# EHT_Dimmer.net
KiCad netlist of a schematic drawn in EAGLE
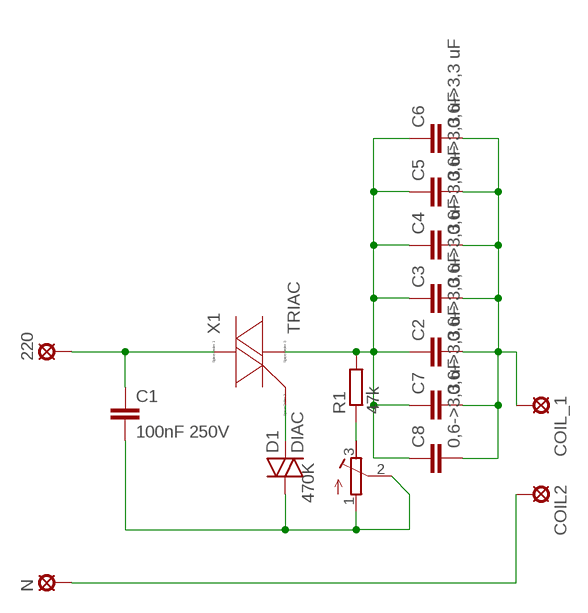
[diagram p0: schematic, sheet 1]

(export (version "E")
  (design (tool "Eeschema 10.0.6"))
  (components
    (comp (ref "220")
      (value "LSP10")
      (footprint "eagle-import:LSP10")
      (libsource (lib "eagle-import") (part "LSP10"))
    )
    (comp (ref "470K")
      (value "R-TRIMM3339P")
      (footprint "eagle-import:RTRIM3339P")
      (libsource (lib "eagle-import") (part "R-TRIMM3339P"))
    )
    (comp (ref "C1")
      (value "100nF 250V")
      (footprint "eagle-import:C102_152-062X184")
      (libsource (lib "eagle-import") (part "C-EU102_152-062X184"))
    )
    (comp (ref "C2")
      (value "0,6->3,3 uF")
      (footprint "eagle-import:C102_152-062X184")
      (libsource (lib "eagle-import") (part "C-EU102_152-062X184"))
    )
    (comp (ref "C3")
      (value "0,6->3,3 uF")
      (footprint "eagle-import:C102_152-062X184")
      (libsource (lib "eagle-import") (part "C-EU102_152-062X184"))
    )
    (comp (ref "C4")
      (value "0,6->3,3 uF")
      (footprint "eagle-import:C102_152-062X184")
      (libsource (lib "eagle-import") (part "C-EU102_152-062X184"))
    )
    (comp (ref "C5")
      (value "0,6->3,3 uF")
      (footprint "eagle-import:C102_152-062X184")
      (libsource (lib "eagle-import") (part "C-EU102_152-062X184"))
    )
    (comp (ref "C6")
      (value "0,6->3,3 uF")
      (footprint "eagle-import:C102_152-062X184")
      (libsource (lib "eagle-import") (part "C-EU102_152-062X184"))
    )
    (comp (ref "C7")
      (value "0,6->3,3 uF")
      (footprint "eagle-import:C102_152-062X184")
      (libsource (lib "eagle-import") (part "C-EU102_152-062X184"))
    )
    (comp (ref "C8")
      (value "0,6->3,3 uF")
      (footprint "eagle-import:C102_152-062X184")
      (libsource (lib "eagle-import") (part "C-EU102_152-062X184"))
    )
    (comp (ref "COIL2")
      (value "LSP10")
      (footprint "eagle-import:LSP10")
      (libsource (lib "eagle-import") (part "LSP10"))
    )
    (comp (ref "COIL_1")
      (value "LSP10")
      (footprint "eagle-import:LSP10")
      (libsource (lib "eagle-import") (part "LSP10"))
    )
    (comp (ref "D1")
      (value "DIAC")
      (footprint "eagle-import:GT32")
      (libsource (lib "eagle-import") (part "DIAC-GT32"))
    )
    (comp (ref "N")
      (value "LSP10")
      (footprint "eagle-import:LSP10")
      (libsource (lib "eagle-import") (part "LSP10"))
    )
    (comp (ref "R1")
      (value "47k")
      (footprint "eagle-import:0207_10")
      (libsource (lib "eagle-import") (part "R-EU_0207/10"))
    )
    (comp (ref "X1")
      (value "TRIAC")
      (footprint "eagle-import:BR220S")
      (libsource (lib "eagle-import") (part "TRIAC"))
    )
  )
  (nets
    (net (code "1") (name "Net-(470K-A)") (class "Default")
      (node (ref "470K") (pin "1") (pinfunction "A_1") (pintype "passive"))
      (node (ref "470K") (pin "2") (pinfunction "S_2") (pintype "passive"))
      (node (ref "C1") (pin "2") (pinfunction "2_2") (pintype "passive"))
      (node (ref "D1") (pin "1") (pinfunction "1_1") (pintype "passive"))
    )
    (net (code "2") (name "Net-(470K-E)") (class "Default")
      (node (ref "470K") (pin "3") (pinfunction "E_3") (pintype "passive"))
      (node (ref "R1") (pin "1") (pinfunction "1_1") (pintype "passive"))
    )
    (net (code "3") (name "Net-(C2-Pad2)") (class "Default")
      (node (ref "C2") (pin "2") (pinfunction "2_2") (pintype "passive"))
      (node (ref "C3") (pin "2") (pinfunction "2_2") (pintype "passive"))
      (node (ref "C4") (pin "2") (pinfunction "2_2") (pintype "passive"))
      (node (ref "C5") (pin "2") (pinfunction "2_2") (pintype "passive"))
      (node (ref "C6") (pin "2") (pinfunction "2_2") (pintype "passive"))
      (node (ref "C7") (pin "2") (pinfunction "2_2") (pintype "passive"))
      (node (ref "C8") (pin "2") (pinfunction "2_2") (pintype "passive"))
      (node (ref "COIL_1") (pin "MP") (pinfunction "MP_MP") (pintype "passive"))
    )
    (net (code "4") (name "Net-(COIL2-PadMP)") (class "Default")
      (node (ref "COIL2") (pin "MP") (pinfunction "MP_MP") (pintype "passive"))
      (node (ref "N") (pin "MP") (pinfunction "MP_MP") (pintype "passive"))
    )
    (net (code "5") (name "Net-(X1-G)") (class "Default")
      (node (ref "D1") (pin "2") (pinfunction "2_2") (pintype "passive"))
      (node (ref "X1") (pin "T1") (pinfunction "G_T1") (pintype "passive"))
    )
    (net (code "6") (name "Net-(X1-MT1)") (class "Default")
      (node (ref "C2") (pin "1") (pinfunction "1_1") (pintype "passive"))
      (node (ref "C3") (pin "1") (pinfunction "1_1") (pintype "passive"))
      (node (ref "C4") (pin "1") (pinfunction "1_1") (pintype "passive"))
      (node (ref "C5") (pin "1") (pinfunction "1_1") (pintype "passive"))
      (node (ref "C6") (pin "1") (pinfunction "1_1") (pintype "passive"))
      (node (ref "C7") (pin "1") (pinfunction "1_1") (pintype "passive"))
      (node (ref "C8") (pin "1") (pinfunction "1_1") (pintype "passive"))
      (node (ref "R1") (pin "2") (pinfunction "2_2") (pintype "passive"))
      (node (ref "X1") (pin "T2") (pinfunction "MT1_T2") (pintype "passive"))
    )
    (net (code "7") (name "Net-(X1-MT2)") (class "Default")
      (node (ref "220") (pin "MP") (pinfunction "MP_MP") (pintype "passive"))
      (node (ref "C1") (pin "1") (pinfunction "1_1") (pintype "passive"))
      (node (ref "X1") (pin "T3") (pinfunction "MT2_T3") (pintype "passive"))
    )
  )
)
